# PowerSupply-5V-3_3V-v11.net
KiCad netlist of a schematic drawn in EAGLE
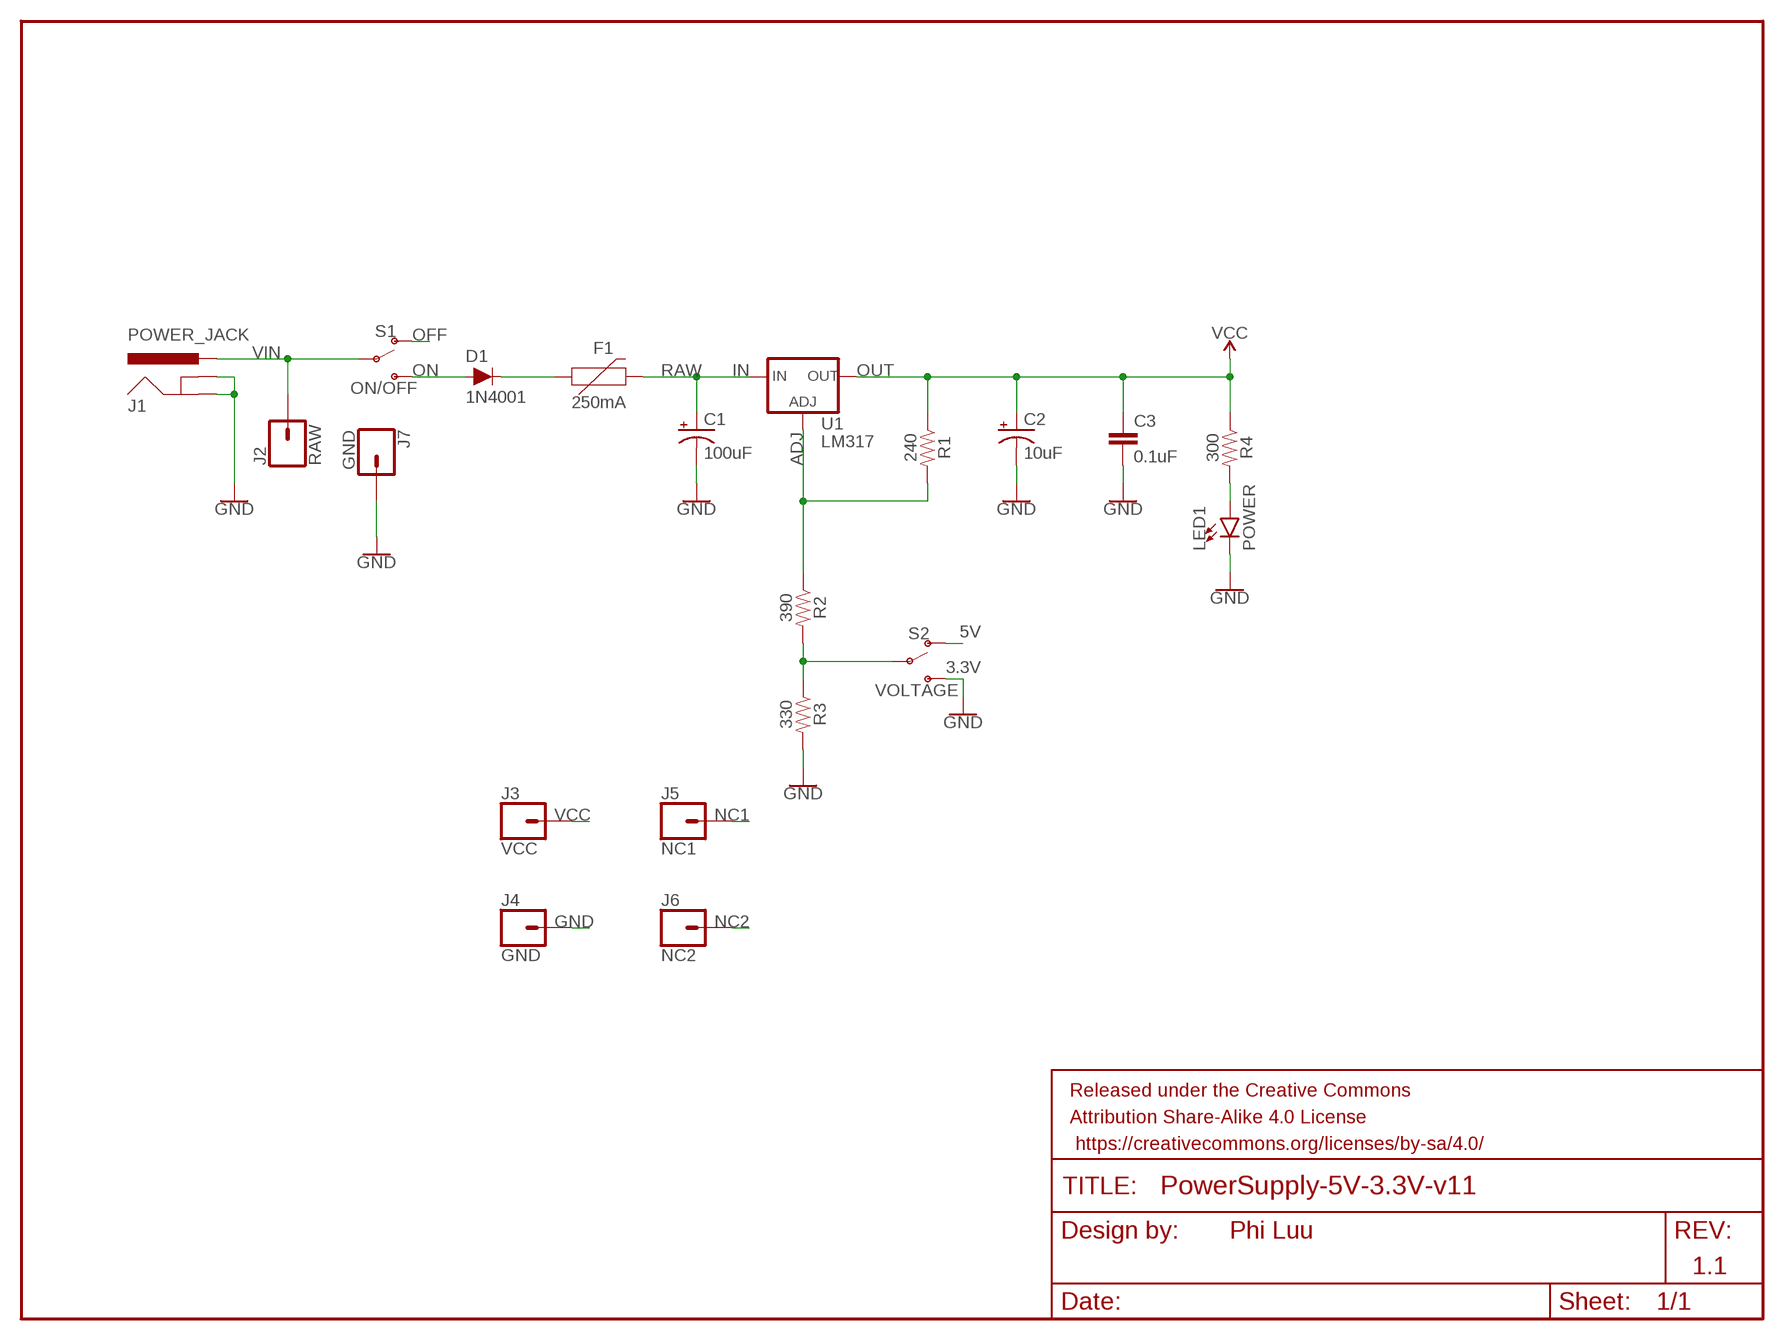
[diagram p0: schematic, sheet 1]

(export (version "E")
  (design (tool "Eeschema 10.0.6"))
  (components
    (comp (ref "C1")
      (value "100uF")
      (footprint "eagle-import:CPOL-RADIAL-2.5MM-6.5MM")
      (libsource (lib "eagle-import") (part "100UF-POLAR-RADIAL-2.5MM-25V-20%"))
    )
    (comp (ref "C2")
      (value "10uF")
      (footprint "eagle-import:CPOL-RADIAL-2.5MM-5MM")
      (libsource (lib "eagle-import") (part "10UF-POLAR-RADIAL-2.5MM-25V-20%"))
    )
    (comp (ref "C3")
      (value "0.1uF")
      (footprint "eagle-import:CAP-PTH-SMALL-KIT")
      (libsource (lib "eagle-import") (part "0.1UF-KIT-EZ-50V-20%"))
    )
    (comp (ref "D1")
      (value "1N4001")
      (footprint "eagle-import:DIODE-1N4001")
      (libsource (lib "eagle-import") (part "DIODE-PTH"))
    )
    (comp (ref "F1")
      (value "250mA")
      (footprint "eagle-import:PTH")
      (libsource (lib "eagle-import") (part "PPTC_PTH"))
    )
    (comp (ref "FRAME1")
      (value "FRAME-LETTER")
      (footprint "eagle-import:CREATIVE_COMMONS")
      (libsource (lib "eagle-import") (part "FRAME-LETTER"))
    )
    (comp (ref "J1")
      (value "POWER_JACK")
      (footprint "eagle-import:POWER_JACK_PTH")
      (libsource (lib "eagle-import") (part "POWER_JACK"))
    )
    (comp (ref "J2")
      (value "RAW")
      (footprint "eagle-import:1X01")
      (libsource (lib "eagle-import") (part "CONN_01"))
    )
    (comp (ref "J3")
      (value "VCC")
      (footprint "eagle-import:1X01")
      (libsource (lib "eagle-import") (part "CONN_01"))
    )
    (comp (ref "J4")
      (value "GND")
      (footprint "eagle-import:1X01")
      (libsource (lib "eagle-import") (part "CONN_01"))
    )
    (comp (ref "J5")
      (value "NC1")
      (footprint "eagle-import:1X01")
      (libsource (lib "eagle-import") (part "CONN_01"))
    )
    (comp (ref "J6")
      (value "NC2")
      (footprint "eagle-import:1X01")
      (libsource (lib "eagle-import") (part "CONN_01"))
    )
    (comp (ref "J7")
      (value "GND")
      (footprint "eagle-import:1X01")
      (libsource (lib "eagle-import") (part "CONN_01"))
    )
    (comp (ref "LED1")
      (value "POWER")
      (footprint "eagle-import:LED_5MM")
      (libsource (lib "eagle-import") (part "LED5MM"))
    )
    (comp (ref "R1")
      (value "240")
      (footprint "eagle-import:AXIAL-0.3")
      (libsource (lib "eagle-import") (part "1KOHM-HORIZ-1/4W-5%"))
    )
    (comp (ref "R2")
      (value "390")
      (footprint "eagle-import:AXIAL-0.3")
      (libsource (lib "eagle-import") (part "1KOHM-HORIZ-1/4W-5%"))
    )
    (comp (ref "R3")
      (value "330")
      (footprint "eagle-import:AXIAL-0.3")
      (libsource (lib "eagle-import") (part "1KOHM-HORIZ-1/4W-5%"))
    )
    (comp (ref "R4")
      (value "300")
      (footprint "eagle-import:AXIAL-0.3")
      (libsource (lib "eagle-import") (part "1KOHM-HORIZ-1/4W-5%"))
    )
    (comp (ref "S1")
      (value "ON/OFF")
      (footprint "eagle-import:SWITCH_SPDT_PTH_11.6X4.0MM")
      (libsource (lib "eagle-import") (part "SWITCH-SPDT-PTH-11.6X4.0MM"))
    )
    (comp (ref "S2")
      (value "VOLTAGE")
      (footprint "eagle-import:SWITCH_SPDT_PTH_11.6X4.0MM")
      (libsource (lib "eagle-import") (part "SWITCH-SPDT-PTH-11.6X4.0MM"))
    )
    (comp (ref "U1")
      (value "LM317")
      (footprint "eagle-import:TO220-ADJ")
      (libsource (lib "eagle-import") (part "V_REG_317SINK"))
    )
  )
  (nets
    (net (code "1") (name "/5V") (class "Default")
      (node (ref "S2") (pin "1") (pinfunction "O_1") (pintype "passive"))
    )
    (net (code "2") (name "/ADJ") (class "Default")
      (node (ref "R1") (pin "P$2") (pinfunction "2_P$2") (pintype "passive"))
      (node (ref "R2") (pin "P$1") (pinfunction "1_P$1") (pintype "passive"))
      (node (ref "U1") (pin "ADJ") (pinfunction "ADJ_ADJ") (pintype "input"))
    )
    (net (code "3") (name "/NC1") (class "Default")
      (node (ref "J5") (pin "1") (pinfunction "1_1") (pintype "passive"))
    )
    (net (code "4") (name "/NC2") (class "Default")
      (node (ref "J6") (pin "1") (pinfunction "1_1") (pintype "passive"))
    )
    (net (code "5") (name "/OFF") (class "Default")
      (node (ref "S1") (pin "1") (pinfunction "O_1") (pintype "passive"))
    )
    (net (code "6") (name "/ON") (class "Default")
      (node (ref "D1") (pin "A") (pinfunction "A_A") (pintype "passive"))
      (node (ref "S1") (pin "3") (pinfunction "S_3") (pintype "passive"))
    )
    (net (code "7") (name "/RAW") (class "Default")
      (node (ref "C1") (pin "1") (pinfunction "+_1") (pintype "passive"))
      (node (ref "F1") (pin "P$2") (pinfunction "2_P$2") (pintype "bidirectional"))
      (node (ref "U1") (pin "IN") (pinfunction "IN_IN") (pintype "input"))
    )
    (net (code "8") (name "/VIN") (class "Default")
      (node (ref "J1") (pin "PWR") (pinfunction "PWR_PWR") (pintype "bidirectional"))
      (node (ref "J2") (pin "1") (pinfunction "1_1") (pintype "passive"))
      (node (ref "S1") (pin "2") (pinfunction "P_2") (pintype "passive"))
    )
    (net (code "9") (name "GND") (class "Default")
      (node (ref "C1") (pin "2") (pinfunction "-_2") (pintype "passive"))
      (node (ref "C2") (pin "2") (pinfunction "-_2") (pintype "passive"))
      (node (ref "C3") (pin "2") (pinfunction "2_2") (pintype "passive"))
      (node (ref "J1") (pin "GND") (pinfunction "GND_GND") (pintype "bidirectional"))
      (node (ref "J1") (pin "GNDBREAK") (pinfunction "GNDBREAK_GNDBREAK") (pintype "bidirectional"))
      (node (ref "J4") (pin "1") (pinfunction "1_1") (pintype "passive"))
      (node (ref "J7") (pin "1") (pinfunction "1_1") (pintype "passive"))
      (node (ref "LED1") (pin "K") (pinfunction "C_K") (pintype "passive"))
      (node (ref "R3") (pin "P$2") (pinfunction "2_P$2") (pintype "passive"))
      (node (ref "S2") (pin "3") (pinfunction "S_3") (pintype "passive"))
    )
    (net (code "10") (name "Net-(F1-1)") (class "Default")
      (node (ref "D1") (pin "C") (pinfunction "C_C") (pintype "passive"))
      (node (ref "F1") (pin "P$1") (pinfunction "1_P$1") (pintype "bidirectional"))
    )
    (net (code "11") (name "Net-(R2-2)") (class "Default")
      (node (ref "R2") (pin "P$2") (pinfunction "2_P$2") (pintype "passive"))
      (node (ref "R3") (pin "P$1") (pinfunction "1_P$1") (pintype "passive"))
      (node (ref "S2") (pin "2") (pinfunction "P_2") (pintype "passive"))
    )
    (net (code "12") (name "Net-(R4-2)") (class "Default")
      (node (ref "LED1") (pin "A") (pinfunction "A_A") (pintype "passive"))
      (node (ref "R4") (pin "P$2") (pinfunction "2_P$2") (pintype "passive"))
    )
    (net (code "13") (name "VCC") (class "Default")
      (node (ref "C2") (pin "1") (pinfunction "+_1") (pintype "passive"))
      (node (ref "C3") (pin "1") (pinfunction "1_1") (pintype "passive"))
      (node (ref "J3") (pin "1") (pinfunction "1_1") (pintype "passive"))
      (node (ref "R1") (pin "P$1") (pinfunction "1_P$1") (pintype "passive"))
      (node (ref "R4") (pin "P$1") (pinfunction "1_P$1") (pintype "passive"))
      (node (ref "U1") (pin "OUT") (pinfunction "OUT_OUT") (pintype "output"))
    )
  )
)
